# 7segement4digits1badidea-mk-5_0-smd.net
KiCad netlist of a schematic drawn in EAGLE
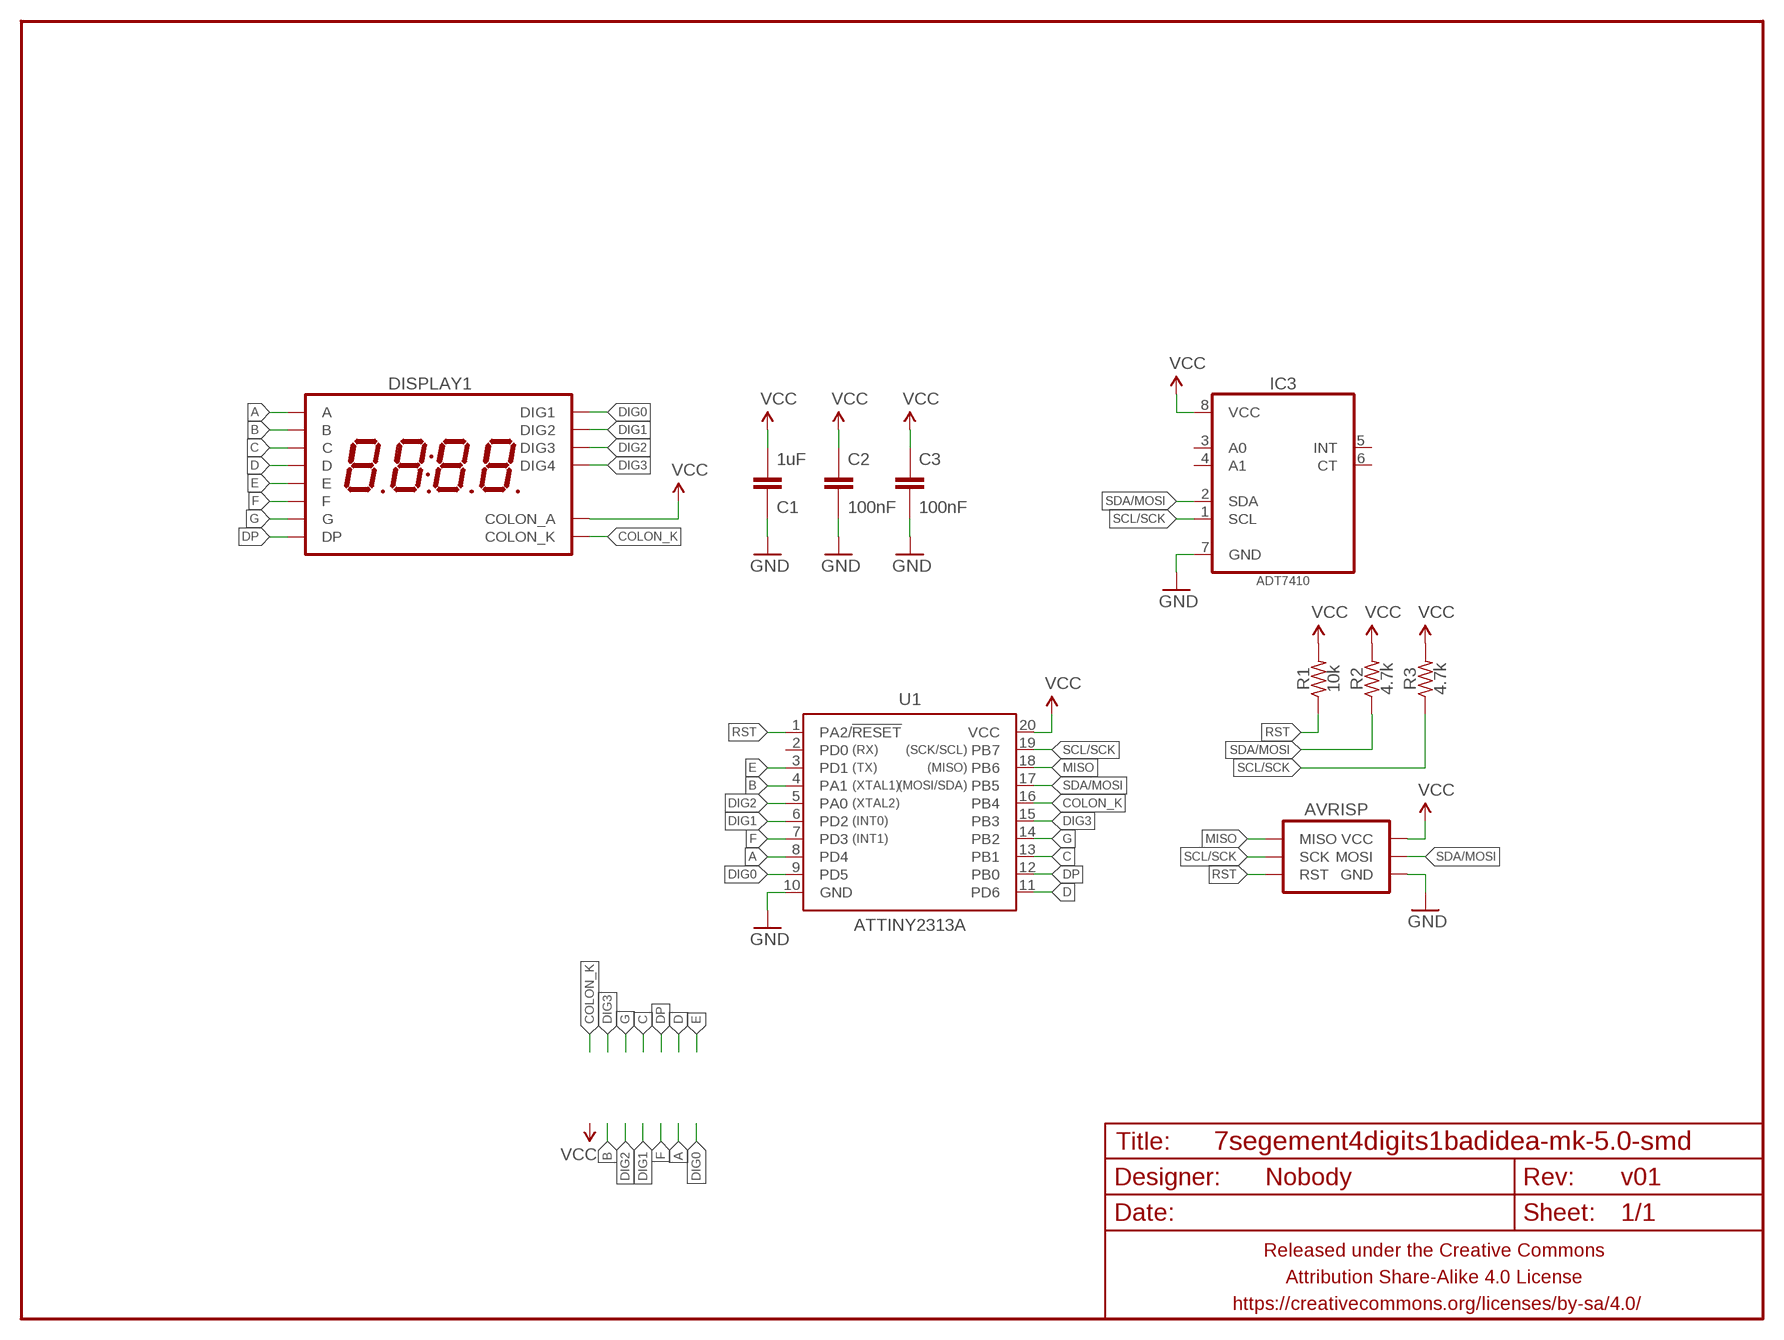
[diagram p0: schematic, sheet 1]

(export (version "E")
  (design (tool "Eeschema 10.0.6"))
  (components
    (comp (ref "AVRISP")
      (value "AVR_SPI_PRG_6AVR-JST-PTH-RA-I2C")
      (footprint "eagle-import:AVR-JST-6-PTH-RA-I2C")
      (libsource (lib "eagle-import") (part "AVR_SPI_PRG_6AVR-JST-PTH-RA-I2C"))
    )
    (comp (ref "C1")
      (value "1uF")
      (footprint "eagle-import:C0805")
      (libsource (lib "eagle-import") (part "CAPACITOR-CERAMICC0805"))
    )
    (comp (ref "C2")
      (value "100nF")
      (footprint "eagle-import:C0805")
      (libsource (lib "eagle-import") (part "CAPACITOR-CERAMICC0805"))
    )
    (comp (ref "C3")
      (value "100nF")
      (footprint "eagle-import:C0805")
      (libsource (lib "eagle-import") (part "CAPACITOR-CERAMICC0805"))
    )
    (comp (ref "DISPLAY1")
      (value "7SEG_4DIGIT_COLONADAFRUIT_0.56IN")
      (footprint "eagle-import:7SEG_4DIG")
      (libsource (lib "eagle-import") (part "7SEG_4DIGIT_COLONADAFRUIT_0.56IN"))
    )
    (comp (ref "FRAME1")
      (value "FRAME-LETTERNO_PACKAGE")
      (footprint "eagle-import:DUMMY")
      (fields (field (name "DESIGNER") "Nobody"))
      (libsource (lib "eagle-import") (part "FRAME-LETTERNO_PACKAGE"))
    )
    (comp (ref "IC3")
      (value "ADT7410")
      (footprint "eagle-import:SOIC127P600X175-8N")
      (fields (field (name "MPN") "ADT7410TRZ"))
      (libsource (lib "eagle-import") (part "ADT7410TRZSOIC8N"))
    )
    (comp (ref "R1")
      (value "10k")
      (footprint "eagle-import:R0805")
      (libsource (lib "eagle-import") (part "RESISTORR0805"))
    )
    (comp (ref "R2")
      (value "4.7k")
      (footprint "eagle-import:R0805")
      (libsource (lib "eagle-import") (part "RESISTORR0805"))
    )
    (comp (ref "R3")
      (value "4.7k")
      (footprint "eagle-import:R0805")
      (libsource (lib "eagle-import") (part "RESISTORR0805"))
    )
    (comp (ref "U1")
      (value "ATTINY2313A")
      (footprint "eagle-import:SOIC20W-SLIM")
      (libsource (lib "eagle-import") (part "ATTINY2313ASOIC-SLIM"))
    )
  )
  (nets
    (net (code "1") (name "A") (class "Default")
      (node (ref "DISPLAY1") (pin "P$13") (pinfunction "A_P$13") (pintype "passive"))
      (node (ref "U1") (pin "8") (pinfunction "PD4_8") (pintype "bidirectional"))
    )
    (net (code "2") (name "B") (class "Default")
      (node (ref "DISPLAY1") (pin "P$9") (pinfunction "B_P$9") (pintype "passive"))
      (node (ref "U1") (pin "4") (pinfunction "PA1_4") (pintype "bidirectional"))
    )
    (net (code "3") (name "C") (class "Default")
      (node (ref "DISPLAY1") (pin "P$4") (pinfunction "C_P$4") (pintype "passive"))
      (node (ref "U1") (pin "13") (pinfunction "PB1_13") (pintype "bidirectional"))
    )
    (net (code "4") (name "COLON_K") (class "Default")
      (node (ref "DISPLAY1") (pin "P$7") (pinfunction "COLON_K_P$7") (pintype "passive"))
      (node (ref "U1") (pin "16") (pinfunction "PB4_16") (pintype "bidirectional"))
    )
    (net (code "5") (name "D") (class "Default")
      (node (ref "DISPLAY1") (pin "P$2") (pinfunction "D_P$2") (pintype "passive"))
      (node (ref "U1") (pin "11") (pinfunction "PD6_11") (pintype "bidirectional"))
    )
    (net (code "6") (name "DIG0") (class "Default")
      (node (ref "DISPLAY1") (pin "P$14") (pinfunction "DIG1_P$14") (pintype "passive"))
      (node (ref "U1") (pin "9") (pinfunction "PD5_9") (pintype "bidirectional"))
    )
    (net (code "7") (name "DIG1") (class "Default")
      (node (ref "DISPLAY1") (pin "P$11") (pinfunction "DIG2_P$11") (pintype "passive"))
      (node (ref "U1") (pin "6") (pinfunction "PD2_6") (pintype "bidirectional"))
    )
    (net (code "8") (name "DIG2") (class "Default")
      (node (ref "DISPLAY1") (pin "P$10") (pinfunction "DIG3_P$10") (pintype "passive"))
      (node (ref "U1") (pin "5") (pinfunction "PA0_5") (pintype "bidirectional"))
    )
    (net (code "9") (name "DIG3") (class "Default")
      (node (ref "DISPLAY1") (pin "P$6") (pinfunction "DIG4_P$6") (pintype "passive"))
      (node (ref "U1") (pin "15") (pinfunction "PB3_15") (pintype "bidirectional"))
    )
    (net (code "10") (name "DP") (class "Default")
      (node (ref "DISPLAY1") (pin "P$3") (pinfunction "DP_P$3") (pintype "passive"))
      (node (ref "U1") (pin "12") (pinfunction "PB0_12") (pintype "bidirectional"))
    )
    (net (code "11") (name "E") (class "Default")
      (node (ref "DISPLAY1") (pin "P$1") (pinfunction "E_P$1") (pintype "passive"))
      (node (ref "U1") (pin "3") (pinfunction "PD1_3") (pintype "bidirectional"))
    )
    (net (code "12") (name "F") (class "Default")
      (node (ref "DISPLAY1") (pin "P$12") (pinfunction "F_P$12") (pintype "passive"))
      (node (ref "U1") (pin "7") (pinfunction "PD3_7") (pintype "bidirectional"))
    )
    (net (code "13") (name "G") (class "Default")
      (node (ref "DISPLAY1") (pin "P$5") (pinfunction "G_P$5") (pintype "passive"))
      (node (ref "U1") (pin "14") (pinfunction "PB2_14") (pintype "bidirectional"))
    )
    (net (code "14") (name "GND") (class "Default")
      (node (ref "AVRISP") (pin "GND") (pinfunction "GND_GND") (pintype "passive"))
      (node (ref "C1") (pin "1") (pinfunction "1_1") (pintype "passive"))
      (node (ref "C2") (pin "2") (pinfunction "2_2") (pintype "passive"))
      (node (ref "C3") (pin "2") (pinfunction "2_2") (pintype "passive"))
      (node (ref "IC3") (pin "7") (pinfunction "GND_7") (pintype "passive"))
      (node (ref "U1") (pin "10") (pinfunction "GND_10") (pintype "bidirectional"))
    )
    (net (code "15") (name "MISO") (class "Default")
      (node (ref "AVRISP") (pin "MISO") (pinfunction "MISO_MISO") (pintype "passive"))
      (node (ref "U1") (pin "18") (pinfunction "PB6_18") (pintype "bidirectional"))
    )
    (net (code "16") (name "RST") (class "Default")
      (node (ref "AVRISP") (pin "RESET") (pinfunction "RST_RESET") (pintype "passive"))
      (node (ref "R1") (pin "1") (pinfunction "1_1") (pintype "passive"))
      (node (ref "U1") (pin "1") (pinfunction "PA2/~{RESET}_1") (pintype "bidirectional"))
    )
    (net (code "17") (name "SCL{slash}SCK") (class "Default")
      (node (ref "AVRISP") (pin "SCK") (pinfunction "SCK_SCK") (pintype "passive"))
      (node (ref "IC3") (pin "1") (pinfunction "SCL_1") (pintype "input"))
      (node (ref "R3") (pin "1") (pinfunction "1_1") (pintype "passive"))
      (node (ref "U1") (pin "19") (pinfunction "PB7_19") (pintype "bidirectional"))
    )
    (net (code "18") (name "SDA{slash}MOSI") (class "Default")
      (node (ref "AVRISP") (pin "MOSI/SDA") (pinfunction "MOSI_MOSI/SDA") (pintype "passive"))
      (node (ref "IC3") (pin "2") (pinfunction "SDA_2") (pintype "bidirectional"))
      (node (ref "R2") (pin "1") (pinfunction "1_1") (pintype "passive"))
      (node (ref "U1") (pin "17") (pinfunction "PB5_17") (pintype "bidirectional"))
    )
    (net (code "19") (name "VCC") (class "Default")
      (node (ref "AVRISP") (pin "VCC") (pinfunction "VCC_VCC") (pintype "passive"))
      (node (ref "C1") (pin "2") (pinfunction "2_2") (pintype "passive"))
      (node (ref "C2") (pin "1") (pinfunction "1_1") (pintype "passive"))
      (node (ref "C3") (pin "1") (pinfunction "1_1") (pintype "passive"))
      (node (ref "DISPLAY1") (pin "P$8") (pinfunction "COLON_A_P$8") (pintype "passive"))
      (node (ref "IC3") (pin "8") (pinfunction "VCC_8") (pintype "power_in"))
      (node (ref "R1") (pin "2") (pinfunction "2_2") (pintype "passive"))
      (node (ref "R2") (pin "2") (pinfunction "2_2") (pintype "passive"))
      (node (ref "R3") (pin "2") (pinfunction "2_2") (pintype "passive"))
      (node (ref "U1") (pin "20") (pinfunction "VCC_20") (pintype "bidirectional"))
    )
    (net (code "20") (name "unconnected-(IC3-A0-Pad3)") (class "Default")
      (node (ref "IC3") (pin "3") (pinfunction "A0_3") (pintype "input"))
    )
    (net (code "21") (name "unconnected-(IC3-A1-Pad4)") (class "Default")
      (node (ref "IC3") (pin "4") (pinfunction "A1_4") (pintype "input"))
    )
    (net (code "22") (name "unconnected-(IC3-CT-Pad6)") (class "Default")
      (node (ref "IC3") (pin "6") (pinfunction "CT_6") (pintype "output"))
    )
    (net (code "23") (name "unconnected-(IC3-INT-Pad5)") (class "Default")
      (node (ref "IC3") (pin "5") (pinfunction "INT_5") (pintype "output"))
    )
    (net (code "24") (name "unconnected-(U1-PD0-Pad2)") (class "Default")
      (node (ref "U1") (pin "2") (pinfunction "PD0_2") (pintype "bidirectional"))
    )
  )
)
